# 808_CB.net
KiCad netlist of a schematic drawn in EAGLE
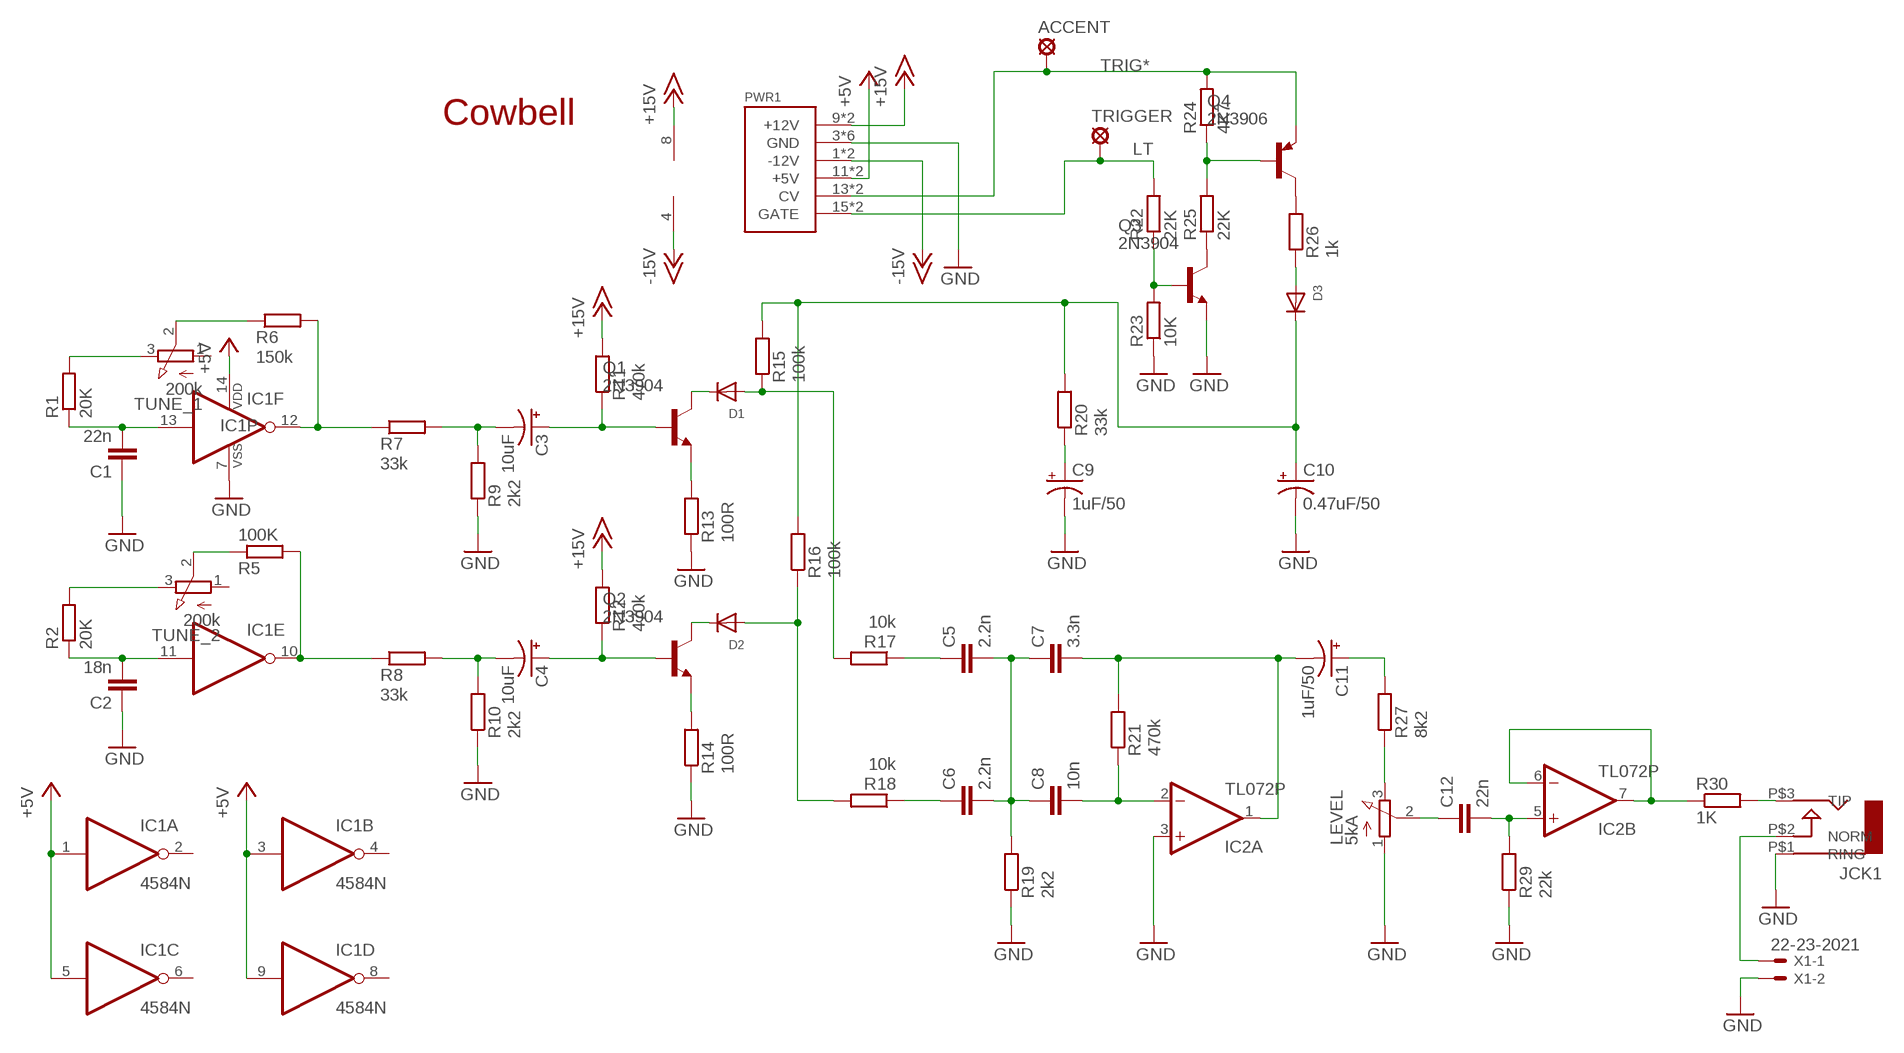
[diagram p0: schematic, sheet 1]

(export (version "E")
  (design (tool "Eeschema 10.0.6"))
  (components
    (comp (ref "ACCENT")
      (value "LSP11")
      (footprint "eagle-import:LSP11")
      (libsource (lib "eagle-import") (part "LSP11"))
    )
    (comp (ref "C1")
      (value "22n")
      (footprint "eagle-import:C035-030X60")
      (libsource (lib "eagle-import") (part "C-EU4MM_PITCH"))
    )
    (comp (ref "C2")
      (value "18n")
      (footprint "eagle-import:C035-030X60")
      (libsource (lib "eagle-import") (part "C-EU4MM_PITCH"))
    )
    (comp (ref "C3")
      (value "10uF")
      (footprint "eagle-import:B45181A")
      (libsource (lib "eagle-import") (part "CPOL-USB45181A"))
    )
    (comp (ref "C4")
      (value "10uF")
      (footprint "eagle-import:B45181A")
      (libsource (lib "eagle-import") (part "CPOL-USB45181A"))
    )
    (comp (ref "C5")
      (value "2.2n")
      (footprint "eagle-import:C035-025X75")
      (libsource (lib "eagle-import") (part "C-EU3.5MM_PITCH"))
    )
    (comp (ref "C6")
      (value "2.2n")
      (footprint "eagle-import:C035-025X75")
      (libsource (lib "eagle-import") (part "C-EU3.5MM_PITCH"))
    )
    (comp (ref "C7")
      (value "3.3n")
      (footprint "eagle-import:C035-025X75")
      (libsource (lib "eagle-import") (part "C-EU3.5MM_PITCH"))
    )
    (comp (ref "C8")
      (value "10n")
      (footprint "eagle-import:C035-025X75")
      (libsource (lib "eagle-import") (part "C-EU3.5MM_PITCH"))
    )
    (comp (ref "C9")
      (value "1uF/50")
      (footprint "eagle-import:B45181A")
      (libsource (lib "eagle-import") (part "CPOL-USB45181A"))
    )
    (comp (ref "C10")
      (value "0.47uF/50")
      (footprint "eagle-import:B45181A")
      (libsource (lib "eagle-import") (part "CPOL-USB45181A"))
    )
    (comp (ref "C11")
      (value "1uF/50")
      (footprint "eagle-import:B45181A")
      (libsource (lib "eagle-import") (part "CPOL-USB45181A"))
    )
    (comp (ref "C12")
      (value "22n")
      (footprint "eagle-import:C035-025X75")
      (libsource (lib "eagle-import") (part "C-EU3.5MM_PITCH"))
    )
    (comp (ref "D1")
      (value "DIODEDO-1N4148")
      (footprint "eagle-import:DO-1N4148")
      (libsource (lib "eagle-import") (part "DIODEDO-1N4148"))
    )
    (comp (ref "D2")
      (value "DIODEDO-1N4148")
      (footprint "eagle-import:DO-1N4148")
      (libsource (lib "eagle-import") (part "DIODEDO-1N4148"))
    )
    (comp (ref "D3")
      (value "DIODEDO-1N4148")
      (footprint "eagle-import:DO-1N4148")
      (libsource (lib "eagle-import") (part "DIODEDO-1N4148"))
    )
    (comp (ref "IC1")
      (value "4584N")
      (footprint "eagle-import:DIL14")
      (libsource (lib "eagle-import") (part "4584N"))
    )
    (comp (ref "IC2")
      (value "TL072P")
      (footprint "eagle-import:DIL08")
      (libsource (lib "eagle-import") (part "TL072P"))
    )
    (comp (ref "JCK1")
      (value "AUDIO-JACK")
      (footprint "eagle-import:ERTHENVAR-JACK-90DEG")
      (libsource (lib "eagle-import") (part "AUDIO-JACK"))
    )
    (comp (ref "LEVEL")
      (value "5kA")
      (footprint "eagle-import:3RP_1610N")
      (libsource (lib "eagle-import") (part "3RP/1610N"))
    )
    (comp (ref "PWR1")
      (value "POWER")
      (footprint "eagle-import:POWER_16")
      (libsource (lib "eagle-import") (part "POWER"))
    )
    (comp (ref "Q1")
      (value "2N3904")
      (footprint "eagle-import:TO92")
      (libsource (lib "eagle-import") (part "2N3904"))
    )
    (comp (ref "Q2")
      (value "2N3904")
      (footprint "eagle-import:TO92")
      (libsource (lib "eagle-import") (part "2N3904"))
    )
    (comp (ref "Q3")
      (value "2N3904")
      (footprint "eagle-import:TO92")
      (libsource (lib "eagle-import") (part "2N3904"))
    )
    (comp (ref "Q4")
      (value "2N3906")
      (footprint "eagle-import:TO92")
      (libsource (lib "eagle-import") (part "2N3906"))
    )
    (comp (ref "R1")
      (value "20K")
      (footprint "eagle-import:0207_5V")
      (libsource (lib "eagle-import") (part "R-EU_0207/5V"))
    )
    (comp (ref "R2")
      (value "20K")
      (footprint "eagle-import:0207_5V")
      (libsource (lib "eagle-import") (part "R-EU_0207/5V"))
    )
    (comp (ref "R5")
      (value "100K")
      (footprint "eagle-import:0207_5V")
      (libsource (lib "eagle-import") (part "R-EU_0207/5V"))
    )
    (comp (ref "R6")
      (value "150k")
      (footprint "eagle-import:0207_5V")
      (libsource (lib "eagle-import") (part "R-EU_0207/5V"))
    )
    (comp (ref "R7")
      (value "33k")
      (footprint "eagle-import:0207_5V")
      (libsource (lib "eagle-import") (part "R-EU_0207/5V"))
    )
    (comp (ref "R8")
      (value "33k")
      (footprint "eagle-import:0207_7")
      (libsource (lib "eagle-import") (part "R-EU_0207/7"))
    )
    (comp (ref "R9")
      (value "2k2")
      (footprint "eagle-import:0207_5V")
      (libsource (lib "eagle-import") (part "R-EU_0207/5V"))
    )
    (comp (ref "R10")
      (value "2k2")
      (footprint "eagle-import:0207_5V")
      (libsource (lib "eagle-import") (part "R-EU_0207/5V"))
    )
    (comp (ref "R11")
      (value "470k")
      (footprint "eagle-import:0207_5V")
      (libsource (lib "eagle-import") (part "R-EU_0207/5V"))
    )
    (comp (ref "R12")
      (value "470k")
      (footprint "eagle-import:0207_5V")
      (libsource (lib "eagle-import") (part "R-EU_0207/5V"))
    )
    (comp (ref "R13")
      (value "100R")
      (footprint "eagle-import:0207_5V")
      (libsource (lib "eagle-import") (part "R-EU_0207/5V"))
    )
    (comp (ref "R14")
      (value "100R")
      (footprint "eagle-import:0207_5V")
      (libsource (lib "eagle-import") (part "R-EU_0207/5V"))
    )
    (comp (ref "R15")
      (value "100k")
      (footprint "eagle-import:0207_5V")
      (libsource (lib "eagle-import") (part "R-EU_0207/5V"))
    )
    (comp (ref "R16")
      (value "100k")
      (footprint "eagle-import:0207_5V")
      (libsource (lib "eagle-import") (part "R-EU_0207/5V"))
    )
    (comp (ref "R17")
      (value "10k")
      (footprint "eagle-import:0207_5V")
      (libsource (lib "eagle-import") (part "R-EU_0207/5V"))
    )
    (comp (ref "R18")
      (value "10k")
      (footprint "eagle-import:0207_5V")
      (libsource (lib "eagle-import") (part "R-EU_0207/5V"))
    )
    (comp (ref "R19")
      (value "2k2")
      (footprint "eagle-import:0207_5V")
      (libsource (lib "eagle-import") (part "R-EU_0207/5V"))
    )
    (comp (ref "R20")
      (value "33k")
      (footprint "eagle-import:0207_5V")
      (libsource (lib "eagle-import") (part "R-EU_0207/5V"))
    )
    (comp (ref "R21")
      (value "470k")
      (footprint "eagle-import:0207_5V")
      (libsource (lib "eagle-import") (part "R-EU_0207/5V"))
    )
    (comp (ref "R22")
      (value "22K")
      (footprint "eagle-import:0207_5V")
      (libsource (lib "eagle-import") (part "R-EU_0207/5V"))
    )
    (comp (ref "R23")
      (value "10K")
      (footprint "eagle-import:0207_5V")
      (libsource (lib "eagle-import") (part "R-EU_0207/5V"))
    )
    (comp (ref "R24")
      (value "4K7")
      (footprint "eagle-import:0207_5V")
      (libsource (lib "eagle-import") (part "R-EU_0207/5V"))
    )
    (comp (ref "R25")
      (value "22K")
      (footprint "eagle-import:0207_5V")
      (libsource (lib "eagle-import") (part "R-EU_0207/5V"))
    )
    (comp (ref "R26")
      (value "1k")
      (footprint "eagle-import:0207_5V")
      (libsource (lib "eagle-import") (part "R-EU_0207/5V"))
    )
    (comp (ref "R27")
      (value "8k2")
      (footprint "eagle-import:0207_5V")
      (libsource (lib "eagle-import") (part "R-EU_0207/5V"))
    )
    (comp (ref "R29")
      (value "22k")
      (footprint "eagle-import:0207_5V")
      (libsource (lib "eagle-import") (part "R-EU_0207/5V"))
    )
    (comp (ref "R30")
      (value "1K")
      (footprint "eagle-import:0207_5V")
      (libsource (lib "eagle-import") (part "R-EU_0207/5V"))
    )
    (comp (ref "TRIGGER")
      (value "LSP11")
      (footprint "eagle-import:LSP11")
      (libsource (lib "eagle-import") (part "LSP11"))
    )
    (comp (ref "TUNE_1")
      (value "200k")
      (footprint "eagle-import:3RP_1610N")
      (libsource (lib "eagle-import") (part "3RP/1610N"))
    )
    (comp (ref "TUNE_2")
      (value "200k")
      (footprint "eagle-import:3RP_1610N")
      (libsource (lib "eagle-import") (part "3RP/1610N"))
    )
    (comp (ref "X1")
      (value "22-23-2021")
      (footprint "eagle-import:22-23-2021")
      (fields (field (name "MF") "MOLEX"))
      (libsource (lib "eagle-import") (part "22-23-2021"))
    )
  )
  (nets
    (net (code "1") (name "+5V") (class "Default")
      (node (ref "IC1") (pin "1") (pinfunction "I_1") (pintype "input"))
      (node (ref "IC1") (pin "14") (pinfunction "VDD_14") (pintype "power_in"))
      (node (ref "IC1") (pin "3") (pinfunction "I_3") (pintype "input"))
      (node (ref "IC1") (pin "5") (pinfunction "I_5") (pintype "input"))
      (node (ref "IC1") (pin "9") (pinfunction "I_9") (pintype "input"))
      (node (ref "PWR1") (pin "11") (pinfunction "+5V_11") (pintype "bidirectional"))
      (node (ref "PWR1") (pin "12") (pinfunction "+5V_12") (pintype "bidirectional"))
    )
    (net (code "2") (name "+15V") (class "Default")
      (node (ref "IC2") (pin "8") (pinfunction "V+_8") (pintype "power_in"))
      (node (ref "PWR1") (pin "10") (pinfunction "+12V_10") (pintype "bidirectional"))
      (node (ref "PWR1") (pin "9") (pinfunction "+12V_9") (pintype "bidirectional"))
      (node (ref "R11") (pin "2") (pinfunction "2_2") (pintype "passive"))
      (node (ref "R12") (pin "2") (pinfunction "2_2") (pintype "passive"))
    )
    (net (code "3") (name "-15V") (class "Default")
      (node (ref "IC2") (pin "4") (pinfunction "V-_4") (pintype "power_in"))
      (node (ref "PWR1") (pin "1") (pinfunction "-12V_1") (pintype "bidirectional"))
      (node (ref "PWR1") (pin "2") (pinfunction "-12V_2") (pintype "bidirectional"))
    )
    (net (code "4") (name "/LT") (class "Default")
      (node (ref "PWR1") (pin "15") (pinfunction "GATE_15") (pintype "bidirectional"))
      (node (ref "PWR1") (pin "16") (pinfunction "GATE_16") (pintype "bidirectional"))
      (node (ref "R22") (pin "2") (pinfunction "2_2") (pintype "passive"))
      (node (ref "TRIGGER") (pin "MP") (pinfunction "MP_MP") (pintype "passive"))
    )
    (net (code "5") (name "/TRIG*") (class "Default")
      (node (ref "ACCENT") (pin "MP") (pinfunction "MP_MP") (pintype "passive"))
      (node (ref "PWR1") (pin "13") (pinfunction "CV_13") (pintype "bidirectional"))
      (node (ref "PWR1") (pin "14") (pinfunction "CV_14") (pintype "bidirectional"))
      (node (ref "Q4") (pin "3") (pinfunction "E_3") (pintype "passive"))
      (node (ref "R24") (pin "2") (pinfunction "2_2") (pintype "passive"))
    )
    (net (code "6") (name "GND") (class "Default")
      (node (ref "C1") (pin "P$1") (pinfunction "1_P$1") (pintype "passive"))
      (node (ref "C10") (pin "-") (pinfunction "-_-") (pintype "passive"))
      (node (ref "C2") (pin "P$1") (pinfunction "1_P$1") (pintype "passive"))
      (node (ref "C9") (pin "-") (pinfunction "-_-") (pintype "passive"))
      (node (ref "IC1") (pin "7") (pinfunction "VSS_7") (pintype "power_in"))
      (node (ref "IC2") (pin "3") (pinfunction "+IN_3") (pintype "input"))
      (node (ref "JCK1") (pin "P$1") (pinfunction "RING_P$1") (pintype "bidirectional"))
      (node (ref "LEVEL") (pin "1") (pinfunction "A_1") (pintype "passive"))
      (node (ref "PWR1") (pin "3") (pinfunction "GND_3") (pintype "bidirectional"))
      (node (ref "PWR1") (pin "4") (pinfunction "GND_4") (pintype "bidirectional"))
      (node (ref "PWR1") (pin "5") (pinfunction "GND_5") (pintype "bidirectional"))
      (node (ref "PWR1") (pin "6") (pinfunction "GND_6") (pintype "bidirectional"))
      (node (ref "PWR1") (pin "7") (pinfunction "GND_7") (pintype "bidirectional"))
      (node (ref "PWR1") (pin "8") (pinfunction "GND_8") (pintype "bidirectional"))
      (node (ref "Q3") (pin "3") (pinfunction "E_3") (pintype "passive"))
      (node (ref "R10") (pin "1") (pinfunction "1_1") (pintype "passive"))
      (node (ref "R13") (pin "1") (pinfunction "1_1") (pintype "passive"))
      (node (ref "R14") (pin "1") (pinfunction "1_1") (pintype "passive"))
      (node (ref "R19") (pin "1") (pinfunction "1_1") (pintype "passive"))
      (node (ref "R23") (pin "1") (pinfunction "1_1") (pintype "passive"))
      (node (ref "R29") (pin "1") (pinfunction "1_1") (pintype "passive"))
      (node (ref "R9") (pin "1") (pinfunction "1_1") (pintype "passive"))
      (node (ref "X1") (pin "2") (pinfunction "S_2") (pintype "passive"))
    )
    (net (code "7") (name "Net-(C1-2)") (class "Default")
      (node (ref "C1") (pin "P$2") (pinfunction "2_P$2") (pintype "passive"))
      (node (ref "IC1") (pin "13") (pinfunction "I_13") (pintype "input"))
      (node (ref "R1") (pin "1") (pinfunction "1_1") (pintype "passive"))
    )
    (net (code "8") (name "Net-(C2-2)") (class "Default")
      (node (ref "C2") (pin "P$2") (pinfunction "2_P$2") (pintype "passive"))
      (node (ref "IC1") (pin "11") (pinfunction "I_11") (pintype "input"))
      (node (ref "R2") (pin "1") (pinfunction "1_1") (pintype "passive"))
    )
    (net (code "9") (name "Net-(C3-Pad-)") (class "Default")
      (node (ref "C3") (pin "-") (pinfunction "-_-") (pintype "passive"))
      (node (ref "R7") (pin "2") (pinfunction "2_2") (pintype "passive"))
      (node (ref "R9") (pin "2") (pinfunction "2_2") (pintype "passive"))
    )
    (net (code "10") (name "Net-(C4-Pad-)") (class "Default")
      (node (ref "C4") (pin "-") (pinfunction "-_-") (pintype "passive"))
      (node (ref "R10") (pin "2") (pinfunction "2_2") (pintype "passive"))
      (node (ref "R8") (pin "2") (pinfunction "2_2") (pintype "passive"))
    )
    (net (code "11") (name "Net-(C5-1)") (class "Default")
      (node (ref "C5") (pin "P$1") (pinfunction "1_P$1") (pintype "passive"))
      (node (ref "R17") (pin "1") (pinfunction "1_1") (pintype "passive"))
    )
    (net (code "12") (name "Net-(C5-2)") (class "Default")
      (node (ref "C5") (pin "P$2") (pinfunction "2_P$2") (pintype "passive"))
      (node (ref "C6") (pin "P$2") (pinfunction "2_P$2") (pintype "passive"))
      (node (ref "C7") (pin "P$1") (pinfunction "1_P$1") (pintype "passive"))
      (node (ref "C8") (pin "P$1") (pinfunction "1_P$1") (pintype "passive"))
      (node (ref "R19") (pin "2") (pinfunction "2_2") (pintype "passive"))
    )
    (net (code "13") (name "Net-(C6-1)") (class "Default")
      (node (ref "C6") (pin "P$1") (pinfunction "1_P$1") (pintype "passive"))
      (node (ref "R18") (pin "1") (pinfunction "1_1") (pintype "passive"))
    )
    (net (code "14") (name "Net-(C7-2)") (class "Default")
      (node (ref "C11") (pin "-") (pinfunction "-_-") (pintype "passive"))
      (node (ref "C7") (pin "P$2") (pinfunction "2_P$2") (pintype "passive"))
      (node (ref "IC2") (pin "1") (pinfunction "OUT_1") (pintype "output"))
      (node (ref "R21") (pin "2") (pinfunction "2_2") (pintype "passive"))
    )
    (net (code "15") (name "Net-(C8-2)") (class "Default")
      (node (ref "C8") (pin "P$2") (pinfunction "2_P$2") (pintype "passive"))
      (node (ref "IC2") (pin "2") (pinfunction "-IN_2") (pintype "input"))
      (node (ref "R21") (pin "1") (pinfunction "1_1") (pintype "passive"))
    )
    (net (code "16") (name "Net-(C9-Pad+)") (class "Default")
      (node (ref "C9") (pin "+") (pinfunction "+_+") (pintype "passive"))
      (node (ref "R20") (pin "1") (pinfunction "1_1") (pintype "passive"))
    )
    (net (code "17") (name "Net-(C10-Pad+)") (class "Default")
      (node (ref "C10") (pin "+") (pinfunction "+_+") (pintype "passive"))
      (node (ref "D3") (pin "C") (pinfunction "C_C") (pintype "passive"))
      (node (ref "R15") (pin "2") (pinfunction "2_2") (pintype "passive"))
      (node (ref "R16") (pin "2") (pinfunction "2_2") (pintype "passive"))
      (node (ref "R20") (pin "2") (pinfunction "2_2") (pintype "passive"))
    )
    (net (code "18") (name "Net-(C11-Pad+)") (class "Default")
      (node (ref "C11") (pin "+") (pinfunction "+_+") (pintype "passive"))
      (node (ref "R27") (pin "2") (pinfunction "2_2") (pintype "passive"))
    )
    (net (code "19") (name "Net-(C12-1)") (class "Default")
      (node (ref "C12") (pin "P$1") (pinfunction "1_P$1") (pintype "passive"))
      (node (ref "LEVEL") (pin "2") (pinfunction "S_2") (pintype "passive"))
    )
    (net (code "20") (name "Net-(C12-2)") (class "Default")
      (node (ref "C12") (pin "P$2") (pinfunction "2_P$2") (pintype "passive"))
      (node (ref "IC2") (pin "5") (pinfunction "+IN_5") (pintype "input"))
      (node (ref "R29") (pin "2") (pinfunction "2_2") (pintype "passive"))
    )
    (net (code "21") (name "Net-(D1-PadA)") (class "Default")
      (node (ref "D1") (pin "A") (pinfunction "A_A") (pintype "passive"))
      (node (ref "R15") (pin "1") (pinfunction "1_1") (pintype "passive"))
      (node (ref "R17") (pin "2") (pinfunction "2_2") (pintype "passive"))
    )
    (net (code "22") (name "Net-(D2-PadA)") (class "Default")
      (node (ref "D2") (pin "A") (pinfunction "A_A") (pintype "passive"))
      (node (ref "R16") (pin "1") (pinfunction "1_1") (pintype "passive"))
      (node (ref "R18") (pin "2") (pinfunction "2_2") (pintype "passive"))
    )
    (net (code "23") (name "Net-(D3-PadA)") (class "Default")
      (node (ref "D3") (pin "A") (pinfunction "A_A") (pintype "passive"))
      (node (ref "R26") (pin "1") (pinfunction "1_1") (pintype "passive"))
    )
    (net (code "24") (name "Net-(IC1E-O)") (class "Default")
      (node (ref "IC1") (pin "10") (pinfunction "O_10") (pintype "output"))
      (node (ref "R5") (pin "2") (pinfunction "2_2") (pintype "passive"))
      (node (ref "R8") (pin "1") (pinfunction "1_1") (pintype "passive"))
    )
    (net (code "25") (name "Net-(IC1F-O)") (class "Default")
      (node (ref "IC1") (pin "12") (pinfunction "O_12") (pintype "output"))
      (node (ref "R6") (pin "2") (pinfunction "2_2") (pintype "passive"))
      (node (ref "R7") (pin "1") (pinfunction "1_1") (pintype "passive"))
    )
    (net (code "26") (name "Net-(IC2B--IN)") (class "Default")
      (node (ref "IC2") (pin "6") (pinfunction "-IN_6") (pintype "input"))
      (node (ref "IC2") (pin "7") (pinfunction "OUT_7") (pintype "output"))
      (node (ref "R30") (pin "1") (pinfunction "1_1") (pintype "passive"))
    )
    (net (code "27") (name "Net-(JCK1-NORM)") (class "Default")
      (node (ref "JCK1") (pin "P$2") (pinfunction "NORM_P$2") (pintype "bidirectional"))
      (node (ref "X1") (pin "1") (pinfunction "S_1") (pintype "passive"))
    )
    (net (code "28") (name "Net-(JCK1-TIP)") (class "Default")
      (node (ref "JCK1") (pin "P$3") (pinfunction "TIP_P$3") (pintype "bidirectional"))
      (node (ref "R30") (pin "2") (pinfunction "2_2") (pintype "passive"))
    )
    (net (code "29") (name "Net-(LEVEL-E)") (class "Default")
      (node (ref "LEVEL") (pin "3") (pinfunction "E_3") (pintype "passive"))
      (node (ref "R27") (pin "1") (pinfunction "1_1") (pintype "passive"))
    )
    (net (code "30") (name "Net-(Q1-B)") (class "Default")
      (node (ref "C3") (pin "+") (pinfunction "+_+") (pintype "passive"))
      (node (ref "Q1") (pin "2") (pinfunction "B_2") (pintype "passive"))
      (node (ref "R11") (pin "1") (pinfunction "1_1") (pintype "passive"))
    )
    (net (code "31") (name "Net-(Q1-C)") (class "Default")
      (node (ref "D1") (pin "C") (pinfunction "C_C") (pintype "passive"))
      (node (ref "Q1") (pin "1") (pinfunction "C_1") (pintype "passive"))
    )
    (net (code "32") (name "Net-(Q1-E)") (class "Default")
      (node (ref "Q1") (pin "3") (pinfunction "E_3") (pintype "passive"))
      (node (ref "R13") (pin "2") (pinfunction "2_2") (pintype "passive"))
    )
    (net (code "33") (name "Net-(Q2-B)") (class "Default")
      (node (ref "C4") (pin "+") (pinfunction "+_+") (pintype "passive"))
      (node (ref "Q2") (pin "2") (pinfunction "B_2") (pintype "passive"))
      (node (ref "R12") (pin "1") (pinfunction "1_1") (pintype "passive"))
    )
    (net (code "34") (name "Net-(Q2-C)") (class "Default")
      (node (ref "D2") (pin "C") (pinfunction "C_C") (pintype "passive"))
      (node (ref "Q2") (pin "1") (pinfunction "C_1") (pintype "passive"))
    )
    (net (code "35") (name "Net-(Q2-E)") (class "Default")
      (node (ref "Q2") (pin "3") (pinfunction "E_3") (pintype "passive"))
      (node (ref "R14") (pin "2") (pinfunction "2_2") (pintype "passive"))
    )
    (net (code "36") (name "Net-(Q3-B)") (class "Default")
      (node (ref "Q3") (pin "2") (pinfunction "B_2") (pintype "passive"))
      (node (ref "R22") (pin "1") (pinfunction "1_1") (pintype "passive"))
      (node (ref "R23") (pin "2") (pinfunction "2_2") (pintype "passive"))
    )
    (net (code "37") (name "Net-(Q3-C)") (class "Default")
      (node (ref "Q3") (pin "1") (pinfunction "C_1") (pintype "passive"))
      (node (ref "R25") (pin "1") (pinfunction "1_1") (pintype "passive"))
    )
    (net (code "38") (name "Net-(Q4-B)") (class "Default")
      (node (ref "Q4") (pin "2") (pinfunction "B_2") (pintype "passive"))
      (node (ref "R24") (pin "1") (pinfunction "1_1") (pintype "passive"))
      (node (ref "R25") (pin "2") (pinfunction "2_2") (pintype "passive"))
    )
    (net (code "39") (name "Net-(Q4-C)") (class "Default")
      (node (ref "Q4") (pin "1") (pinfunction "C_1") (pintype "passive"))
      (node (ref "R26") (pin "2") (pinfunction "2_2") (pintype "passive"))
    )
    (net (code "40") (name "Net-(TUNE_1-E)") (class "Default")
      (node (ref "R1") (pin "2") (pinfunction "2_2") (pintype "passive"))
      (node (ref "TUNE_1") (pin "3") (pinfunction "E_3") (pintype "passive"))
    )
    (net (code "41") (name "Net-(TUNE_1-S)") (class "Default")
      (node (ref "R6") (pin "1") (pinfunction "1_1") (pintype "passive"))
      (node (ref "TUNE_1") (pin "2") (pinfunction "S_2") (pintype "passive"))
    )
    (net (code "42") (name "Net-(TUNE_2-E)") (class "Default")
      (node (ref "R2") (pin "2") (pinfunction "2_2") (pintype "passive"))
      (node (ref "TUNE_2") (pin "3") (pinfunction "E_3") (pintype "passive"))
    )
    (net (code "43") (name "Net-(TUNE_2-S)") (class "Default")
      (node (ref "R5") (pin "1") (pinfunction "1_1") (pintype "passive"))
      (node (ref "TUNE_2") (pin "2") (pinfunction "S_2") (pintype "passive"))
    )
    (net (code "44") (name "unconnected-(IC1A-O-Pad2)") (class "Default")
      (node (ref "IC1") (pin "2") (pinfunction "O_2") (pintype "output"))
    )
    (net (code "45") (name "unconnected-(IC1B-O-Pad4)") (class "Default")
      (node (ref "IC1") (pin "4") (pinfunction "O_4") (pintype "output"))
    )
    (net (code "46") (name "unconnected-(IC1C-O-Pad6)") (class "Default")
      (node (ref "IC1") (pin "6") (pinfunction "O_6") (pintype "output"))
    )
    (net (code "47") (name "unconnected-(IC1D-O-Pad8)") (class "Default")
      (node (ref "IC1") (pin "8") (pinfunction "O_8") (pintype "output"))
    )
    (net (code "48") (name "unconnected-(TUNE_1-A-Pad1)") (class "Default")
      (node (ref "TUNE_1") (pin "1") (pinfunction "A_1") (pintype "passive"))
    )
    (net (code "49") (name "unconnected-(TUNE_2-A-Pad1)") (class "Default")
      (node (ref "TUNE_2") (pin "1") (pinfunction "A_1") (pintype "passive"))
    )
  )
)
